# Power.net
KiCad netlist of a schematic drawn in Altium Designer
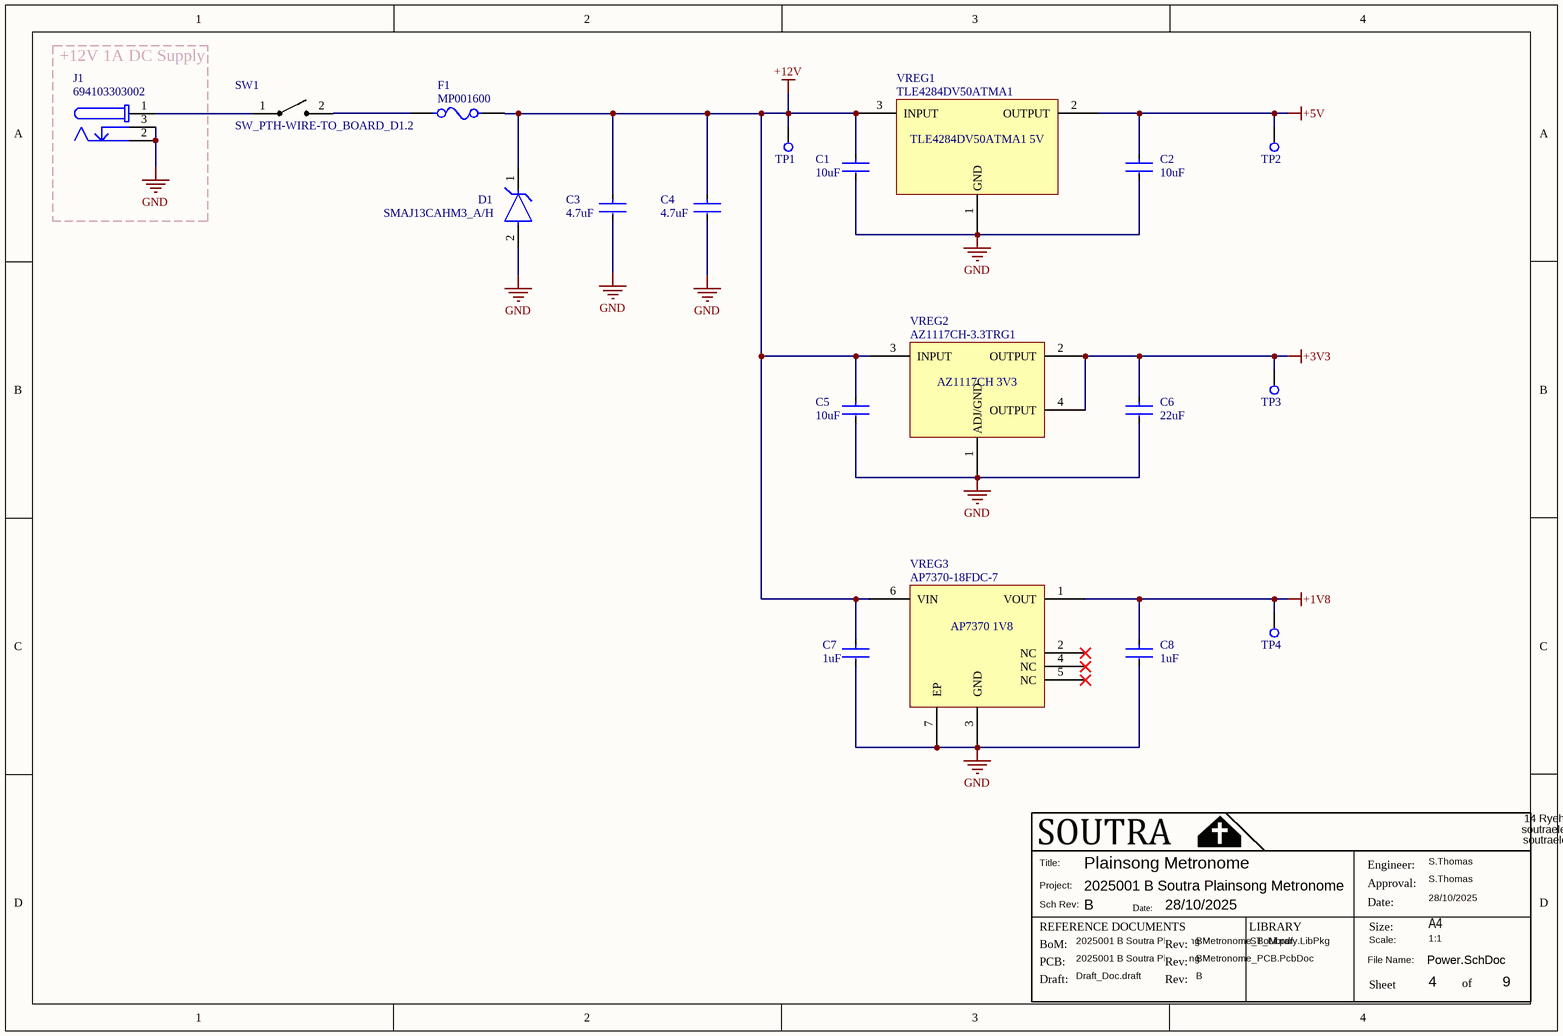
[diagram p0: Power.SchDoc]

(export (version "E")
  (design (tool "Eeschema 10.0.6"))
  (components
    (comp (ref "C1")
      (value "10uF")
      (footprint "CC1206-IPC_A")
      (description "Cap, 10Uf, 25V, Mlcc, 1206 Rohs Compliant: Yes")
      (fields
        (field (name "MANUFACTURER") "Walsin Technologies")
        (field (name "MANUFACTURER PART NUMBER") "1206B106K250CP")
      )
      (libsource (lib "ST_Library") (part "1206B106K250CP"))
    )
    (comp (ref "C2")
      (value "10uF")
      (footprint "CC1206-IPC_A")
      (description "Cap, 10Uf, 25V, Mlcc, 1206 Rohs Compliant: Yes")
      (fields
        (field (name "MANUFACTURER") "Walsin Technologies")
        (field (name "MANUFACTURER PART NUMBER") "1206B106K250CP")
      )
      (libsource (lib "ST_Library") (part "1206B106K250CP"))
    )
    (comp (ref "C3")
      (value "4.7uF")
      (footprint "CC1206-IPC_A")
      (fields
        (field (name "MANUFACTURER") "Samsung")
        (field (name "MANUFACTURER PART NUMBER") "CL31B475KAHNNNE")
      )
      (libsource (lib "ST_Library") (part "CL31B475KAHNNNE"))
    )
    (comp (ref "C4")
      (value "4.7uF")
      (footprint "CC1206-IPC_A")
      (fields
        (field (name "MANUFACTURER") "Samsung")
        (field (name "MANUFACTURER PART NUMBER") "CL31B475KAHNNNE")
      )
      (libsource (lib "ST_Library") (part "CL31B475KAHNNNE"))
    )
    (comp (ref "C5")
      (value "10uF")
      (footprint "CC1206-IPC_A")
      (description "Cap, 10Uf, 25V, Mlcc, 1206 Rohs Compliant: Yes")
      (fields
        (field (name "MANUFACTURER") "Walsin Technologies")
        (field (name "MANUFACTURER PART NUMBER") "1206B106K250CP")
      )
      (libsource (lib "ST_Library") (part "1206B106K250CP"))
    )
    (comp (ref "C6")
      (value "22uF")
      (footprint "CAPC2012X14L")
      (description "SMD Multilayer Ceramic Capacitor, 22 µF, 10 V, 0805 [2012 Metric], ± 20%, X5R, GRM Series")
      (fields
        (field (name "ALTERNATIVE SUPPLIER PART NUMBER") "490-10511-1-ND")
        (field (name "ALTERNATIVE PART") "C2012X5R1A226M125AB")
      )
      (libsource (lib "ST_Library") (part "GRM21BR61A226ME51L"))
    )
    (comp (ref "C7")
      (value "1uF")
      (footprint "CAPC1005X06L")
      (fields
        (field (name "MANUFACTURER") "Yageo")
        (field (name "MANUFACTURER PART NUMBER") "CC0402KRX5R6BB105")
        (field (name "ALTERNATIVE PART") "0402ZD105KAT2A")
      )
      (libsource (lib "ST_Library") (part "CC0402KRX5R6BB105"))
    )
    (comp (ref "C8")
      (value "1uF")
      (footprint "CAPC1005X06L")
      (fields
        (field (name "MANUFACTURER") "Yageo")
        (field (name "MANUFACTURER PART NUMBER") "CC0402KRX5R6BB105")
        (field (name "ALTERNATIVE PART") "0402ZD105KAT2A")
      )
      (libsource (lib "ST_Library") (part "CC0402KRX5R6BB105"))
    )
    (comp (ref "D1")
      (value "SMAJ13CAHM3_A/H")
      (footprint "SODFL511X229-2N")
      (description "TVS Diode, TRANSZORB SMAJ, Bidirectional, 13 V, 21.5 V, DO-214AC (SMA), 2 Pins")
      (fields (field (name "MANUFACTURER") "Vishay"))
      (libsource (lib "ST_Library") (part "SMAJ13CAHM3_A/H"))
    )
    (comp (ref "F1")
      (value "MP001600")
      (footprint "FUSE_3216X08L")
      (description "MULTICOMP PRO MP001600Fuse, Surface Mount, 1.5 A, Fast Acting, 72 VDC, 1206 [3216 Metric]")
      (fields (field (name "MANUFACTURER") "Multicomp"))
      (libsource (lib "ST_Library") (part "MP001600"))
    )
    (comp (ref "J1")
      (value "694103303002")
      (footprint "WURTH_694106301002")
      (description "Circular DC Power Connector")
      (fields (field (name "MANUFACTURER") "Wurth Electronics"))
      (libsource (lib "ST_Library") (part "694103303002"))
    )
    (comp (ref "SW1")
      (value "SW_PTH-WIRE-TO_BOARD_D1.2")
      (footprint "SW_PTH-Wire-to-Board-D1.2")
      (description "PTH Mounting Holes for Wire-to-board switch, 1.2mm diameter, >=17AWG")
      (libsource (lib "ST_Library") (part "SW_PTH-WIRE-TO_BOARD_D1.2"))
    )
    (comp (ref "TP1")
      (value "TP_CIRCLE_R1")
      (footprint "TP_CIRCLE_R1")
      (description "Test Point, SMD, Circular, Radius = 1mm")
      (libsource (lib "ST_Library") (part "TP_CIRCLE_R1"))
    )
    (comp (ref "TP2")
      (value "TP_CIRCLE_R1")
      (footprint "TP_CIRCLE_R1")
      (description "Test Point, SMD, Circular, Radius = 1mm")
      (libsource (lib "ST_Library") (part "TP_CIRCLE_R1"))
    )
    (comp (ref "TP3")
      (value "TP_CIRCLE_R1")
      (footprint "TP_CIRCLE_R1")
      (description "Test Point, SMD, Circular, Radius = 1mm")
      (libsource (lib "ST_Library") (part "TP_CIRCLE_R1"))
    )
    (comp (ref "TP4")
      (value "TP_CIRCLE_R1")
      (footprint "TP_CIRCLE_R1")
      (description "Test Point, SMD, Circular, Radius = 1mm")
      (libsource (lib "ST_Library") (part "TP_CIRCLE_R1"))
    )
    (comp (ref "VREG1")
      (value "TLE4284DV50ATMA1")
      (footprint "TO252-3-11_L")
      (fields (field (name "MANUFACTURER") "Infineon"))
      (libsource (lib "ST_Library") (part "TLE4284DV50ATMA1"))
    )
    (comp (ref "VREG2")
      (value "AZ1117CH-3.3TRG1")
      (footprint "SOT230P700X180-4L")
      (description "Fixed Positive LDO Regulator, 3.3V, 1.3V Dropout, BIPolar, PDSO3")
      (fields (field (name "MANUFACTURER") "Diodes"))
      (libsource (lib "ST_Library") (part "AZ1117CH-3.3TRG1"))
    )
    (comp (ref "VREG3")
      (value "AP7370-18FDC-7")
      (footprint "U-DFN2020EP65P201X201X63_HS-7L")
      (description "Fixed Positive LDO Regulator")
      (fields (field (name "MANUFACTURER") "Diodes"))
      (libsource (lib "ST_Library") (part "AP7370-18FDC-7"))
    )
  )
  (nets
    (net (code "1") (name "+1V8") (class "Default")
      (node (ref "C8") (pin "1") (pinfunction "1_1") (pintype "passive"))
      (node (ref "TP4") (pin "1") (pinfunction "1_1") (pintype "passive"))
      (node (ref "VREG3") (pin "1") (pinfunction "VOUT_1") (pintype "passive"))
    )
    (net (code "2") (name "+3V3") (class "Default")
      (node (ref "C6") (pin "1") (pinfunction "1_1") (pintype "passive"))
      (node (ref "TP3") (pin "1") (pinfunction "1_1") (pintype "passive"))
      (node (ref "VREG2") (pin "2") (pinfunction "OUTPUT_2") (pintype "passive"))
      (node (ref "VREG2") (pin "4") (pinfunction "OUTPUT_4") (pintype "passive"))
    )
    (net (code "3") (name "+5V") (class "Default")
      (node (ref "C2") (pin "1") (pinfunction "1_1") (pintype "passive"))
      (node (ref "TP2") (pin "1") (pinfunction "1_1") (pintype "passive"))
      (node (ref "VREG1") (pin "2") (pinfunction "OUTPUT_2") (pintype "passive"))
    )
    (net (code "4") (name "+12V") (class "Default")
      (node (ref "C1") (pin "1") (pinfunction "1_1") (pintype "passive"))
      (node (ref "C3") (pin "1") (pinfunction "1_1") (pintype "passive"))
      (node (ref "C4") (pin "1") (pinfunction "1_1") (pintype "passive"))
      (node (ref "C5") (pin "1") (pinfunction "1_1") (pintype "passive"))
      (node (ref "C7") (pin "1") (pinfunction "1_1") (pintype "passive"))
      (node (ref "D1") (pin "1") (pinfunction "C_1") (pintype "passive"))
      (node (ref "F1") (pin "2") (pinfunction "2_2") (pintype "passive"))
      (node (ref "TP1") (pin "1") (pinfunction "1_1") (pintype "passive"))
      (node (ref "VREG1") (pin "3") (pinfunction "INPUT_3") (pintype "passive"))
      (node (ref "VREG2") (pin "3") (pinfunction "INPUT_3") (pintype "passive"))
      (node (ref "VREG3") (pin "6") (pinfunction "VIN_6") (pintype "passive"))
    )
    (net (code "5") (name "GND") (class "Default")
      (node (ref "C1") (pin "2") (pinfunction "2_2") (pintype "passive"))
      (node (ref "C2") (pin "2") (pinfunction "2_2") (pintype "passive"))
      (node (ref "C3") (pin "2") (pinfunction "2_2") (pintype "passive"))
      (node (ref "C4") (pin "2") (pinfunction "2_2") (pintype "passive"))
      (node (ref "C5") (pin "2") (pinfunction "2_2") (pintype "passive"))
      (node (ref "C6") (pin "2") (pinfunction "2_2") (pintype "passive"))
      (node (ref "C7") (pin "2") (pinfunction "2_2") (pintype "passive"))
      (node (ref "C8") (pin "2") (pinfunction "2_2") (pintype "passive"))
      (node (ref "D1") (pin "2") (pinfunction "A_2") (pintype "passive"))
      (node (ref "J1") (pin "2") (pinfunction "2_2") (pintype "passive"))
      (node (ref "J1") (pin "3") (pinfunction "3_3") (pintype "passive"))
      (node (ref "VREG1") (pin "1") (pinfunction "GND_1") (pintype "passive"))
      (node (ref "VREG2") (pin "1") (pinfunction "ADJ/GND_1") (pintype "passive"))
      (node (ref "VREG3") (pin "3") (pinfunction "GND_3") (pintype "passive"))
      (node (ref "VREG3") (pin "7") (pinfunction "EP_7") (pintype "passive"))
    )
    (net (code "6") (name "Net-(F1-Pad1)") (class "Default")
      (node (ref "F1") (pin "1") (pinfunction "1_1") (pintype "passive"))
      (node (ref "SW1") (pin "2") (pinfunction "2_2") (pintype "passive"))
    )
    (net (code "7") (name "Net-(J1-Pad1)") (class "Default")
      (node (ref "J1") (pin "1") (pinfunction "1_1") (pintype "passive"))
      (node (ref "SW1") (pin "1") (pinfunction "1_1") (pintype "passive"))
    )
    (net (code "8") (name "unconnected-(VREG3-NC-Pad2)") (class "Default")
      (node (ref "VREG3") (pin "2") (pinfunction "NC_2") (pintype "passive+no_connect"))
    )
    (net (code "9") (name "unconnected-(VREG3-NC-Pad4)") (class "Default")
      (node (ref "VREG3") (pin "4") (pinfunction "NC_4") (pintype "passive+no_connect"))
    )
    (net (code "10") (name "unconnected-(VREG3-NC-Pad5)") (class "Default")
      (node (ref "VREG3") (pin "5") (pinfunction "NC_5") (pintype "passive+no_connect"))
    )
  )
)
